# l1.net
KiCad netlist of a schematic drawn in Altium Designer
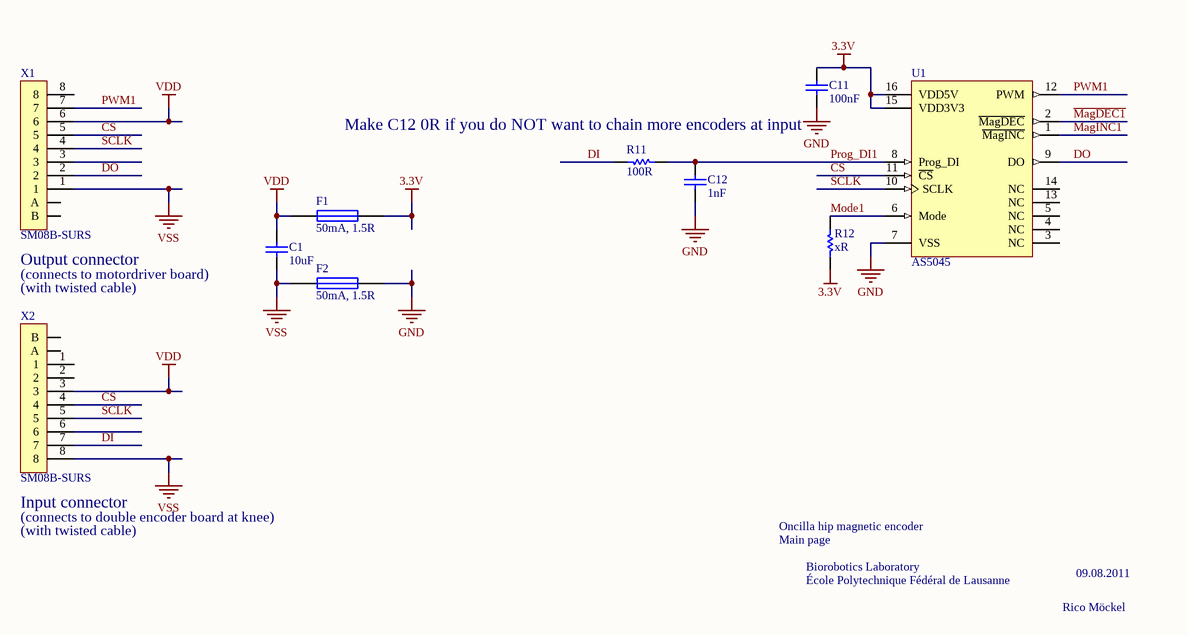
[diagram p0: l1.SchDoc]

(export (version "E")
  (design (tool "Eeschema 10.0.6"))
  (components
    (comp (ref "C1")
      (value "10uF")
      (footprint "CAPC1608L")
      (description "Capacitor")
      (fields (field (name "PUBLISHER") "Altium Limited"))
      (libsource (lib "Miscellaneous Devices") (part "Cap"))
    )
    (comp (ref "C11")
      (value "100nF")
      (footprint "CAPC1608L")
      (description "Capacitor")
      (fields (field (name "PUBLISHER") "Altium Limited"))
      (libsource (lib "Miscellaneous Devices") (part "Cap"))
    )
    (comp (ref "C12")
      (value "1nF")
      (footprint "CAPC1608L")
      (description "Capacitor")
      (fields (field (name "PUBLISHER") "Altium Limited"))
      (libsource (lib "Miscellaneous Devices") (part "Cap"))
    )
    (comp (ref "F1")
      (value "50mA, 1.5R")
      (footprint "RESC1608L")
      (description "Ferrit Bead")
      (fields (field (name "PUBLISHER") "Altium Limited"))
      (libsource (lib "Miscellaneous Devices") (part "Fuse 1"))
    )
    (comp (ref "F2")
      (value "50mA, 1.5R")
      (footprint "RESC1608L")
      (description "Ferrit Bead")
      (fields (field (name "PUBLISHER") "Altium Limited"))
      (libsource (lib "Miscellaneous Devices") (part "Fuse 1"))
    )
    (comp (ref "R11")
      (value "100R")
      (footprint "RESC1608L")
      (description "Resistor")
      (fields (field (name "PUBLISHER") "Altium Limited"))
      (libsource (lib "Miscellaneous Devices") (part "Res1"))
    )
    (comp (ref "R12")
      (value "xR")
      (footprint "RESC1608L")
      (description "Resistor")
      (fields (field (name "PUBLISHER") "Altium Limited"))
      (libsource (lib "") (part "Res1_1"))
    )
    (comp (ref "U1")
      (value "AS5045")
      (footprint "SSOP16")
      (description "12 Bit Programmable Magnetic Rotary Encoder")
      (libsource (lib "Roombots") (part "AS5045"))
    )
    (comp (ref "X1")
      (value "SM08B-SURS")
      (footprint "SM08B-SURS")
      (description "wire-to-board connector")
      (libsource (lib "Roombots") (part "SM08B-SURS"))
    )
    (comp (ref "X2")
      (value "SM08B-SURS")
      (footprint "SM08B-SURS")
      (description "wire-to-board connector")
      (libsource (lib "") (part "SM08B-SURS_1"))
    )
  )
  (nets
    (net (code "1") (name "/DI") (class "Default")
      (node (ref "R11") (pin "1") (pinfunction "1_1") (pintype "passive"))
      (node (ref "X2") (pin "7") (pinfunction "7_7") (pintype "passive"))
    )
    (net (code "2") (name "/DO") (class "Default")
      (node (ref "U1") (pin "9") (pinfunction "DO_9") (pintype "output"))
      (node (ref "X1") (pin "2") (pinfunction "2_2") (pintype "passive"))
    )
    (net (code "3") (name "/Mode1") (class "Default")
      (node (ref "R12") (pin "2") (pinfunction "2_2") (pintype "passive"))
      (node (ref "U1") (pin "6") (pinfunction "Mode_6") (pintype "input"))
    )
    (net (code "4") (name "/PWM1") (class "Default")
      (node (ref "U1") (pin "12") (pinfunction "PWM_12") (pintype "output"))
      (node (ref "X1") (pin "7") (pinfunction "7_7") (pintype "passive"))
    )
    (net (code "5") (name "/Prog_DI1") (class "Default")
      (node (ref "C12") (pin "1") (pinfunction "1_1") (pintype "passive"))
      (node (ref "R11") (pin "2") (pinfunction "2_2") (pintype "passive"))
      (node (ref "U1") (pin "8") (pinfunction "Prog_DI_8") (pintype "input"))
    )
    (net (code "6") (name "/SCLK") (class "Default")
      (node (ref "U1") (pin "10") (pinfunction "SCLK_10") (pintype "input"))
      (node (ref "X1") (pin "4") (pinfunction "4_4") (pintype "passive"))
      (node (ref "X2") (pin "5") (pinfunction "5_5") (pintype "passive"))
    )
    (net (code "7") (name "/~{CS}") (class "Default")
      (node (ref "U1") (pin "11") (pinfunction "~{CS}_11") (pintype "input"))
      (node (ref "X1") (pin "5") (pinfunction "5_5") (pintype "passive"))
      (node (ref "X2") (pin "4") (pinfunction "4_4") (pintype "passive"))
    )
    (net (code "8") (name "/~{MagDEC1}") (class "Default")
      (node (ref "U1") (pin "2") (pinfunction "~{MagDEC}_2") (pintype "output"))
    )
    (net (code "9") (name "/~{MagINC1}") (class "Default")
      (node (ref "U1") (pin "1") (pinfunction "~{MagINC}_1") (pintype "output"))
    )
    (net (code "10") (name "3.3V") (class "Default")
      (node (ref "C11") (pin "1") (pinfunction "1_1") (pintype "passive"))
      (node (ref "F1") (pin "2") (pinfunction "2_2") (pintype "passive"))
      (node (ref "R12") (pin "1") (pinfunction "1_1") (pintype "passive"))
      (node (ref "U1") (pin "15") (pinfunction "VDD3V3_15") (pintype "power_in"))
      (node (ref "U1") (pin "16") (pinfunction "VDD5V_16") (pintype "power_in"))
    )
    (net (code "11") (name "GND") (class "Default")
      (node (ref "C11") (pin "2") (pinfunction "2_2") (pintype "passive"))
      (node (ref "C12") (pin "2") (pinfunction "2_2") (pintype "passive"))
      (node (ref "F2") (pin "2") (pinfunction "2_2") (pintype "passive"))
      (node (ref "U1") (pin "7") (pinfunction "VSS_7") (pintype "power_in"))
    )
    (net (code "12") (name "VDD") (class "Default")
      (node (ref "C1") (pin "2") (pinfunction "2_2") (pintype "passive"))
      (node (ref "F1") (pin "1") (pinfunction "1_1") (pintype "passive"))
      (node (ref "X1") (pin "6") (pinfunction "6_6") (pintype "passive"))
      (node (ref "X2") (pin "3") (pinfunction "3_3") (pintype "passive"))
    )
    (net (code "13") (name "VSS") (class "Default")
      (node (ref "C1") (pin "1") (pinfunction "1_1") (pintype "passive"))
      (node (ref "F2") (pin "1") (pinfunction "1_1") (pintype "passive"))
      (node (ref "X1") (pin "1") (pinfunction "1_1") (pintype "passive"))
      (node (ref "X2") (pin "8") (pinfunction "8_8") (pintype "passive"))
    )
    (net (code "14") (name "unconnected-(U1-NC-Pad3)") (class "Default")
      (node (ref "U1") (pin "3") (pinfunction "NC_3") (pintype "passive"))
    )
    (net (code "15") (name "unconnected-(U1-NC-Pad4)") (class "Default")
      (node (ref "U1") (pin "4") (pinfunction "NC_4") (pintype "passive"))
    )
    (net (code "16") (name "unconnected-(U1-NC-Pad5)") (class "Default")
      (node (ref "U1") (pin "5") (pinfunction "NC_5") (pintype "passive"))
    )
    (net (code "17") (name "unconnected-(U1-NC-Pad13)") (class "Default")
      (node (ref "U1") (pin "13") (pinfunction "NC_13") (pintype "passive"))
    )
    (net (code "18") (name "unconnected-(U1-NC-Pad14)") (class "Default")
      (node (ref "U1") (pin "14") (pinfunction "NC_14") (pintype "passive"))
    )
    (net (code "19") (name "unconnected-(X1-Pad3)") (class "Default")
      (node (ref "X1") (pin "3") (pinfunction "3_3") (pintype "passive"))
    )
    (net (code "20") (name "unconnected-(X1-Pad8)") (class "Default")
      (node (ref "X1") (pin "8") (pinfunction "8_8") (pintype "passive"))
    )
    (net (code "21") (name "unconnected-(X1-PadA)") (class "Default")
      (node (ref "X1") (pin "A") (pinfunction "A_A") (pintype "passive"))
    )
    (net (code "22") (name "unconnected-(X1-PadB)") (class "Default")
      (node (ref "X1") (pin "B") (pinfunction "B_B") (pintype "passive"))
    )
    (net (code "23") (name "unconnected-(X2-Pad1)") (class "Default")
      (node (ref "X2") (pin "1") (pinfunction "1_1") (pintype "passive"))
    )
    (net (code "24") (name "unconnected-(X2-Pad2)") (class "Default")
      (node (ref "X2") (pin "2") (pinfunction "2_2") (pintype "passive"))
    )
    (net (code "25") (name "unconnected-(X2-Pad6)") (class "Default")
      (node (ref "X2") (pin "6") (pinfunction "6_6") (pintype "passive"))
    )
    (net (code "26") (name "unconnected-(X2-PadA)") (class "Default")
      (node (ref "X2") (pin "A") (pinfunction "A_A") (pintype "passive"))
    )
    (net (code "27") (name "unconnected-(X2-PadB)") (class "Default")
      (node (ref "X2") (pin "B") (pinfunction "B_B") (pintype "passive"))
    )
  )
)
